# SCH_Glowing_Heart_2025-11-25.net
KiCad netlist of a schematic drawn in EasyEDA
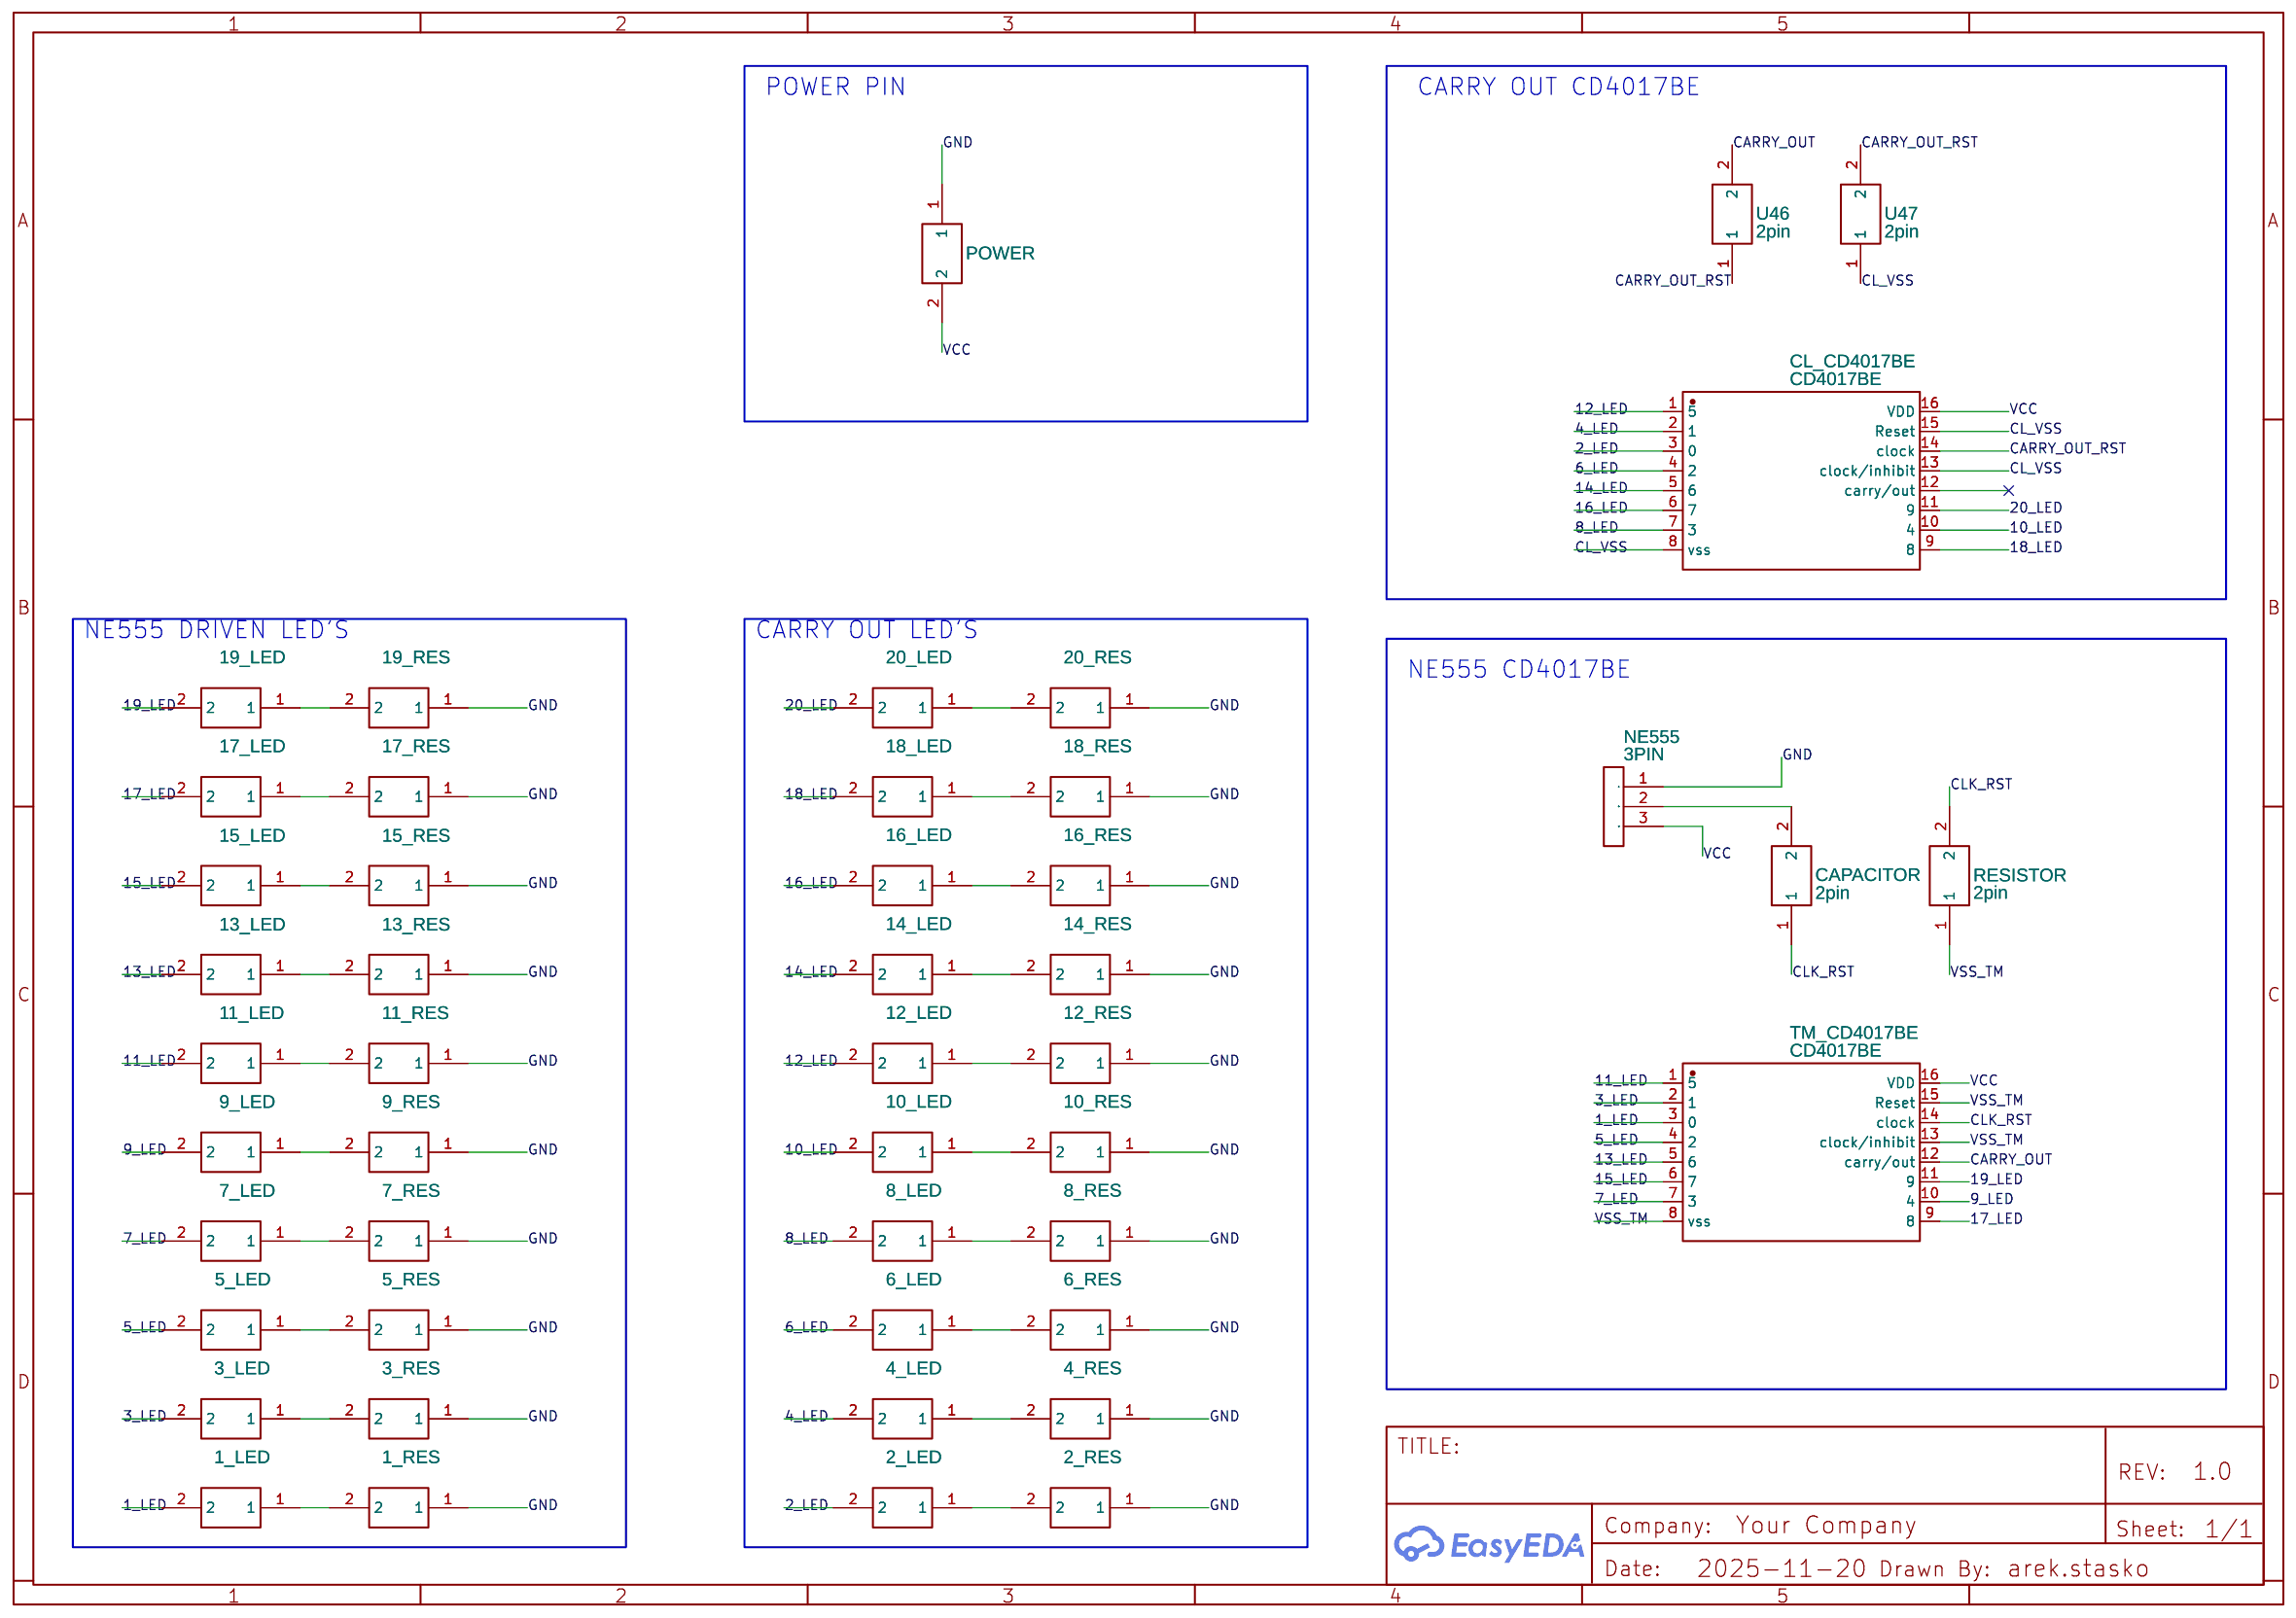
[diagram p0: schematic sheet]

(export (version "E")
  (design (tool "Eeschema 10.0.6"))
  (components
    (comp (ref "1_LED") (value "2pin") (libsource (lib "") (part "2pin_9")))
    (comp (ref "1_RES") (value "2pin") (libsource (lib "") (part "2pin_14")))
    (comp (ref "2_LED") (value "2pin") (libsource (lib "") (part "2pin_42")))
    (comp (ref "2_RES") (value "2pin") (libsource (lib "") (part "2pin_17")))
    (comp (ref "3_LED") (value "2pin") (libsource (lib "") (part "2pin_35")))
    (comp (ref "3_RES") (value "2pin") (libsource (lib "") (part "2pin_22")))
    (comp (ref "4_LED") (value "2pin") (libsource (lib "") (part "2pin_1")))
    (comp (ref "4_RES") (value "2pin") (libsource (lib "") (part "2pin_24")))
    (comp (ref "5_LED") (value "2pin") (libsource (lib "") (part "2pin_26")))
    (comp (ref "5_RES") (value "2pin") (libsource (lib "") (part "2pin_6")))
    (comp (ref "6_LED") (value "2pin") (libsource (lib "") (part "2pin_39")))
    (comp (ref "6_RES") (value "2pin") (libsource (lib "") (part "2pin_10")))
    (comp (ref "7_LED") (value "2pin") (libsource (lib "") (part "2pin_28")))
    (comp (ref "7_RES") (value "2pin") (libsource (lib "") (part "2pin_8")))
    (comp (ref "8_LED") (value "2pin") (libsource (lib "") (part "2pin_32")))
    (comp (ref "8_RES") (value "2pin") (libsource (lib "") (part "2pin_4")))
    (comp (ref "9_LED") (value "2pin") (libsource (lib "") (part "2pin_5")))
    (comp (ref "9_RES") (value "2pin") (libsource (lib "") (part "2pin_33")))
    (comp (ref "10_LED") (value "2pin") (libsource (lib "") (part "2pin_29")))
    (comp (ref "10_RES") (value "2pin") (libsource (lib "") (part "2pin_20")))
    (comp (ref "11_LED") (value "2pin") (libsource (lib "") (part "2pin_15")))
    (comp (ref "11_RES") (value "2pin") (libsource (lib "") (part "2pin_16")))
    (comp (ref "12_LED") (value "2pin") (libsource (lib "") (part "2pin_40")))
    (comp (ref "12_RES") (value "2pin") (libsource (lib "") (part "2pin_34")))
    (comp (ref "13_LED") (value "2pin") (libsource (lib "") (part "2pin_7")))
    (comp (ref "13_RES") (value "2pin") (libsource (lib "") (part "2pin_13")))
    (comp (ref "14_LED") (value "2pin") (libsource (lib "") (part "2pin_27")))
    (comp (ref "14_RES") (value "2pin") (libsource (lib "") (part "2pin_30")))
    (comp (ref "15_LED") (value "2pin") (libsource (lib "") (part "2pin_21")))
    (comp (ref "15_RES") (value "2pin") (libsource (lib "") (part "2pin_37")))
    (comp (ref "16_LED") (value "2pin") (libsource (lib "") (part "2pin_19")))
    (comp (ref "16_RES") (value "2pin") (libsource (lib "") (part "2pin_36")))
    (comp (ref "17_LED") (value "2pin") (libsource (lib "") (part "2pin_38")))
    (comp (ref "17_RES") (value "2pin") (libsource (lib "") (part "2pin_18")))
    (comp (ref "18_LED") (value "2pin") (libsource (lib "") (part "2pin_41")))
    (comp (ref "18_RES") (value "2pin") (libsource (lib "") (part "2pin_43")))
    (comp (ref "19_LED") (value "2pin") (libsource (lib "") (part "2pin_12")))
    (comp (ref "19_RES") (value "2pin") (libsource (lib "") (part "2pin_31")))
    (comp (ref "20_LED") (value "2pin") (libsource (lib "") (part "2pin_23")))
    (comp (ref "20_RES") (value "2pin") (libsource (lib "") (part "2pin_3")))
    (comp (ref "CAPACITOR") (value "2pin") (libsource (lib "") (part "2pin")))
    (comp (ref "CL_CD4017BE") (value "CD4017BE") (libsource (lib "") (part "CD4017BE")))
    (comp (ref "NE555") (value "3PIN") (libsource (lib "") (part "3PIN")))
    (comp (ref "POWER") (value "2pin") (libsource (lib "") (part "2pin_25")))
    (comp (ref "RESISTOR") (value "2pin") (libsource (lib "") (part "2pin_2")))
    (comp (ref "TM_CD4017BE") (value "CD4017BE") (libsource (lib "") (part "CD4017BE_1")))
    (comp (ref "U46") (value "2pin") (libsource (lib "") (part "2pin_11")))
    (comp (ref "U47") (value "2pin") (libsource (lib "") (part "2pin_11")))
  )
  (nets
    (net (code "1") (name "/1_LED") (class "Default")
      (node (ref "1_LED") (pin "2") (pinfunction "2_2") (pintype "unspecified"))
      (node (ref "TM_CD4017BE") (pin "3") (pinfunction "0_3") (pintype "unspecified"))
    )
    (net (code "2") (name "/2_LED") (class "Default")
      (node (ref "2_LED") (pin "2") (pinfunction "2_2") (pintype "unspecified"))
      (node (ref "CL_CD4017BE") (pin "3") (pinfunction "0_3") (pintype "unspecified"))
    )
    (net (code "3") (name "/3_LED") (class "Default")
      (node (ref "3_LED") (pin "2") (pinfunction "2_2") (pintype "unspecified"))
      (node (ref "TM_CD4017BE") (pin "2") (pinfunction "1_2") (pintype "unspecified"))
    )
    (net (code "4") (name "/4_LED") (class "Default")
      (node (ref "4_LED") (pin "2") (pinfunction "2_2") (pintype "unspecified"))
      (node (ref "CL_CD4017BE") (pin "2") (pinfunction "1_2") (pintype "unspecified"))
    )
    (net (code "5") (name "/5_LED") (class "Default")
      (node (ref "5_LED") (pin "2") (pinfunction "2_2") (pintype "unspecified"))
      (node (ref "TM_CD4017BE") (pin "4") (pinfunction "2_4") (pintype "unspecified"))
    )
    (net (code "6") (name "/6_LED") (class "Default")
      (node (ref "6_LED") (pin "2") (pinfunction "2_2") (pintype "unspecified"))
      (node (ref "CL_CD4017BE") (pin "4") (pinfunction "2_4") (pintype "unspecified"))
    )
    (net (code "7") (name "/7_LED") (class "Default")
      (node (ref "7_LED") (pin "2") (pinfunction "2_2") (pintype "unspecified"))
      (node (ref "TM_CD4017BE") (pin "7") (pinfunction "3_7") (pintype "unspecified"))
    )
    (net (code "8") (name "/8_LED") (class "Default")
      (node (ref "8_LED") (pin "2") (pinfunction "2_2") (pintype "unspecified"))
      (node (ref "CL_CD4017BE") (pin "7") (pinfunction "3_7") (pintype "unspecified"))
    )
    (net (code "9") (name "/9_LED") (class "Default")
      (node (ref "9_LED") (pin "2") (pinfunction "2_2") (pintype "unspecified"))
      (node (ref "TM_CD4017BE") (pin "10") (pinfunction "4_10") (pintype "unspecified"))
    )
    (net (code "10") (name "/10_LED") (class "Default")
      (node (ref "10_LED") (pin "2") (pinfunction "2_2") (pintype "unspecified"))
      (node (ref "CL_CD4017BE") (pin "10") (pinfunction "4_10") (pintype "unspecified"))
    )
    (net (code "11") (name "/11_LED") (class "Default")
      (node (ref "11_LED") (pin "2") (pinfunction "2_2") (pintype "unspecified"))
      (node (ref "TM_CD4017BE") (pin "1") (pinfunction "5_1") (pintype "unspecified"))
    )
    (net (code "12") (name "/12_LED") (class "Default")
      (node (ref "12_LED") (pin "2") (pinfunction "2_2") (pintype "unspecified"))
      (node (ref "CL_CD4017BE") (pin "1") (pinfunction "5_1") (pintype "unspecified"))
    )
    (net (code "13") (name "/13_LED") (class "Default")
      (node (ref "13_LED") (pin "2") (pinfunction "2_2") (pintype "unspecified"))
      (node (ref "TM_CD4017BE") (pin "5") (pinfunction "6_5") (pintype "unspecified"))
    )
    (net (code "14") (name "/14_LED") (class "Default")
      (node (ref "14_LED") (pin "2") (pinfunction "2_2") (pintype "unspecified"))
      (node (ref "CL_CD4017BE") (pin "5") (pinfunction "6_5") (pintype "unspecified"))
    )
    (net (code "15") (name "/15_LED") (class "Default")
      (node (ref "15_LED") (pin "2") (pinfunction "2_2") (pintype "unspecified"))
      (node (ref "TM_CD4017BE") (pin "6") (pinfunction "7_6") (pintype "unspecified"))
    )
    (net (code "16") (name "/16_LED") (class "Default")
      (node (ref "16_LED") (pin "2") (pinfunction "2_2") (pintype "unspecified"))
      (node (ref "CL_CD4017BE") (pin "6") (pinfunction "7_6") (pintype "unspecified"))
    )
    (net (code "17") (name "/17_LED") (class "Default")
      (node (ref "17_LED") (pin "2") (pinfunction "2_2") (pintype "unspecified"))
      (node (ref "TM_CD4017BE") (pin "9") (pinfunction "8_9") (pintype "unspecified"))
    )
    (net (code "18") (name "/18_LED") (class "Default")
      (node (ref "18_LED") (pin "2") (pinfunction "2_2") (pintype "unspecified"))
      (node (ref "CL_CD4017BE") (pin "9") (pinfunction "8_9") (pintype "unspecified"))
    )
    (net (code "19") (name "/19_LED") (class "Default")
      (node (ref "19_LED") (pin "2") (pinfunction "2_2") (pintype "unspecified"))
      (node (ref "TM_CD4017BE") (pin "11") (pinfunction "9_11") (pintype "unspecified"))
    )
    (net (code "20") (name "/20_LED") (class "Default")
      (node (ref "20_LED") (pin "2") (pinfunction "2_2") (pintype "unspecified"))
      (node (ref "CL_CD4017BE") (pin "11") (pinfunction "9_11") (pintype "unspecified"))
    )
    (net (code "21") (name "/CARRY_OUT") (class "Default")
      (node (ref "TM_CD4017BE") (pin "12") (pinfunction "carry/out_12") (pintype "unspecified"))
      (node (ref "U46") (pin "2") (pinfunction "2_2") (pintype "unspecified"))
    )
    (net (code "22") (name "/CARRY_OUT_RST") (class "Default")
      (node (ref "CL_CD4017BE") (pin "14") (pinfunction "clock_14") (pintype "unspecified"))
      (node (ref "U46") (pin "1") (pinfunction "1_1") (pintype "unspecified"))
      (node (ref "U47") (pin "2") (pinfunction "2_2") (pintype "unspecified"))
    )
    (net (code "23") (name "/CLK_RST") (class "Default")
      (node (ref "CAPACITOR") (pin "1") (pinfunction "1_1") (pintype "unspecified"))
      (node (ref "RESISTOR") (pin "2") (pinfunction "2_2") (pintype "unspecified"))
      (node (ref "TM_CD4017BE") (pin "14") (pinfunction "clock_14") (pintype "unspecified"))
    )
    (net (code "24") (name "/CL_VSS") (class "Default")
      (node (ref "CL_CD4017BE") (pin "13") (pinfunction "clock/inhibit_13") (pintype "unspecified"))
      (node (ref "CL_CD4017BE") (pin "15") (pinfunction "Reset_15") (pintype "unspecified"))
      (node (ref "CL_CD4017BE") (pin "8") (pinfunction "vss_8") (pintype "unspecified"))
      (node (ref "U47") (pin "1") (pinfunction "1_1") (pintype "unspecified"))
    )
    (net (code "25") (name "/GND") (class "Default")
      (node (ref "10_RES") (pin "1") (pinfunction "1_1") (pintype "unspecified"))
      (node (ref "11_RES") (pin "1") (pinfunction "1_1") (pintype "unspecified"))
      (node (ref "12_RES") (pin "1") (pinfunction "1_1") (pintype "unspecified"))
      (node (ref "13_RES") (pin "1") (pinfunction "1_1") (pintype "unspecified"))
      (node (ref "14_RES") (pin "1") (pinfunction "1_1") (pintype "unspecified"))
      (node (ref "15_RES") (pin "1") (pinfunction "1_1") (pintype "unspecified"))
      (node (ref "16_RES") (pin "1") (pinfunction "1_1") (pintype "unspecified"))
      (node (ref "17_RES") (pin "1") (pinfunction "1_1") (pintype "unspecified"))
      (node (ref "18_RES") (pin "1") (pinfunction "1_1") (pintype "unspecified"))
      (node (ref "19_RES") (pin "1") (pinfunction "1_1") (pintype "unspecified"))
      (node (ref "1_RES") (pin "1") (pinfunction "1_1") (pintype "unspecified"))
      (node (ref "20_RES") (pin "1") (pinfunction "1_1") (pintype "unspecified"))
      (node (ref "2_RES") (pin "1") (pinfunction "1_1") (pintype "unspecified"))
      (node (ref "3_RES") (pin "1") (pinfunction "1_1") (pintype "unspecified"))
      (node (ref "4_RES") (pin "1") (pinfunction "1_1") (pintype "unspecified"))
      (node (ref "5_RES") (pin "1") (pinfunction "1_1") (pintype "unspecified"))
      (node (ref "6_RES") (pin "1") (pinfunction "1_1") (pintype "unspecified"))
      (node (ref "7_RES") (pin "1") (pinfunction "1_1") (pintype "unspecified"))
      (node (ref "8_RES") (pin "1") (pinfunction "1_1") (pintype "unspecified"))
      (node (ref "9_RES") (pin "1") (pinfunction "1_1") (pintype "unspecified"))
      (node (ref "NE555") (pin "1") (pinfunction "1_1") (pintype "unspecified"))
      (node (ref "POWER") (pin "1") (pinfunction "1_1") (pintype "unspecified"))
    )
    (net (code "26") (name "/VCC") (class "Default")
      (node (ref "CL_CD4017BE") (pin "16") (pinfunction "VDD_16") (pintype "unspecified"))
      (node (ref "NE555") (pin "3") (pinfunction "3_3") (pintype "unspecified"))
      (node (ref "POWER") (pin "2") (pinfunction "2_2") (pintype "unspecified"))
      (node (ref "TM_CD4017BE") (pin "16") (pinfunction "VDD_16") (pintype "unspecified"))
    )
    (net (code "27") (name "/VSS_TM") (class "Default")
      (node (ref "RESISTOR") (pin "1") (pinfunction "1_1") (pintype "unspecified"))
      (node (ref "TM_CD4017BE") (pin "13") (pinfunction "clock/inhibit_13") (pintype "unspecified"))
      (node (ref "TM_CD4017BE") (pin "15") (pinfunction "Reset_15") (pintype "unspecified"))
      (node (ref "TM_CD4017BE") (pin "8") (pinfunction "vss_8") (pintype "unspecified"))
    )
    (net (code "28") (name "Net-(1_LED-Pad1)") (class "Default")
      (node (ref "1_LED") (pin "1") (pinfunction "1_1") (pintype "unspecified"))
      (node (ref "1_RES") (pin "2") (pinfunction "2_2") (pintype "unspecified"))
    )
    (net (code "29") (name "Net-(2_LED-Pad1)") (class "Default")
      (node (ref "2_LED") (pin "1") (pinfunction "1_1") (pintype "unspecified"))
      (node (ref "2_RES") (pin "2") (pinfunction "2_2") (pintype "unspecified"))
    )
    (net (code "30") (name "Net-(3_LED-Pad1)") (class "Default")
      (node (ref "3_LED") (pin "1") (pinfunction "1_1") (pintype "unspecified"))
      (node (ref "3_RES") (pin "2") (pinfunction "2_2") (pintype "unspecified"))
    )
    (net (code "31") (name "Net-(4_LED-Pad1)") (class "Default")
      (node (ref "4_LED") (pin "1") (pinfunction "1_1") (pintype "unspecified"))
      (node (ref "4_RES") (pin "2") (pinfunction "2_2") (pintype "unspecified"))
    )
    (net (code "32") (name "Net-(5_LED-Pad1)") (class "Default")
      (node (ref "5_LED") (pin "1") (pinfunction "1_1") (pintype "unspecified"))
      (node (ref "5_RES") (pin "2") (pinfunction "2_2") (pintype "unspecified"))
    )
    (net (code "33") (name "Net-(6_LED-Pad1)") (class "Default")
      (node (ref "6_LED") (pin "1") (pinfunction "1_1") (pintype "unspecified"))
      (node (ref "6_RES") (pin "2") (pinfunction "2_2") (pintype "unspecified"))
    )
    (net (code "34") (name "Net-(7_LED-Pad1)") (class "Default")
      (node (ref "7_LED") (pin "1") (pinfunction "1_1") (pintype "unspecified"))
      (node (ref "7_RES") (pin "2") (pinfunction "2_2") (pintype "unspecified"))
    )
    (net (code "35") (name "Net-(8_LED-Pad1)") (class "Default")
      (node (ref "8_LED") (pin "1") (pinfunction "1_1") (pintype "unspecified"))
      (node (ref "8_RES") (pin "2") (pinfunction "2_2") (pintype "unspecified"))
    )
    (net (code "36") (name "Net-(9_LED-Pad1)") (class "Default")
      (node (ref "9_LED") (pin "1") (pinfunction "1_1") (pintype "unspecified"))
      (node (ref "9_RES") (pin "2") (pinfunction "2_2") (pintype "unspecified"))
    )
    (net (code "37") (name "Net-(10_LED-Pad1)") (class "Default")
      (node (ref "10_LED") (pin "1") (pinfunction "1_1") (pintype "unspecified"))
      (node (ref "10_RES") (pin "2") (pinfunction "2_2") (pintype "unspecified"))
    )
    (net (code "38") (name "Net-(11_LED-Pad1)") (class "Default")
      (node (ref "11_LED") (pin "1") (pinfunction "1_1") (pintype "unspecified"))
      (node (ref "11_RES") (pin "2") (pinfunction "2_2") (pintype "unspecified"))
    )
    (net (code "39") (name "Net-(12_LED-Pad1)") (class "Default")
      (node (ref "12_LED") (pin "1") (pinfunction "1_1") (pintype "unspecified"))
      (node (ref "12_RES") (pin "2") (pinfunction "2_2") (pintype "unspecified"))
    )
    (net (code "40") (name "Net-(13_LED-Pad1)") (class "Default")
      (node (ref "13_LED") (pin "1") (pinfunction "1_1") (pintype "unspecified"))
      (node (ref "13_RES") (pin "2") (pinfunction "2_2") (pintype "unspecified"))
    )
    (net (code "41") (name "Net-(14_LED-Pad1)") (class "Default")
      (node (ref "14_LED") (pin "1") (pinfunction "1_1") (pintype "unspecified"))
      (node (ref "14_RES") (pin "2") (pinfunction "2_2") (pintype "unspecified"))
    )
    (net (code "42") (name "Net-(15_LED-Pad1)") (class "Default")
      (node (ref "15_LED") (pin "1") (pinfunction "1_1") (pintype "unspecified"))
      (node (ref "15_RES") (pin "2") (pinfunction "2_2") (pintype "unspecified"))
    )
    (net (code "43") (name "Net-(16_LED-Pad1)") (class "Default")
      (node (ref "16_LED") (pin "1") (pinfunction "1_1") (pintype "unspecified"))
      (node (ref "16_RES") (pin "2") (pinfunction "2_2") (pintype "unspecified"))
    )
    (net (code "44") (name "Net-(17_LED-Pad1)") (class "Default")
      (node (ref "17_LED") (pin "1") (pinfunction "1_1") (pintype "unspecified"))
      (node (ref "17_RES") (pin "2") (pinfunction "2_2") (pintype "unspecified"))
    )
    (net (code "45") (name "Net-(18_LED-Pad1)") (class "Default")
      (node (ref "18_LED") (pin "1") (pinfunction "1_1") (pintype "unspecified"))
      (node (ref "18_RES") (pin "2") (pinfunction "2_2") (pintype "unspecified"))
    )
    (net (code "46") (name "Net-(19_LED-Pad1)") (class "Default")
      (node (ref "19_LED") (pin "1") (pinfunction "1_1") (pintype "unspecified"))
      (node (ref "19_RES") (pin "2") (pinfunction "2_2") (pintype "unspecified"))
    )
    (net (code "47") (name "Net-(20_LED-Pad1)") (class "Default")
      (node (ref "20_LED") (pin "1") (pinfunction "1_1") (pintype "unspecified"))
      (node (ref "20_RES") (pin "2") (pinfunction "2_2") (pintype "unspecified"))
    )
    (net (code "48") (name "Net-(CAPACITOR-Pad2)") (class "Default")
      (node (ref "CAPACITOR") (pin "2") (pinfunction "2_2") (pintype "unspecified"))
      (node (ref "NE555") (pin "2") (pinfunction "2_2") (pintype "unspecified"))
    )
    (net (code "49") (name "unconnected-(CL_CD4017BE-carry{slash}out-Pad12)") (class "Default")
      (node (ref "CL_CD4017BE") (pin "12") (pinfunction "carry/out_12") (pintype "unspecified+no_connect"))
    )
  )
)
